# SYSTEM.net
KiCad netlist of a schematic drawn in Altium Designer
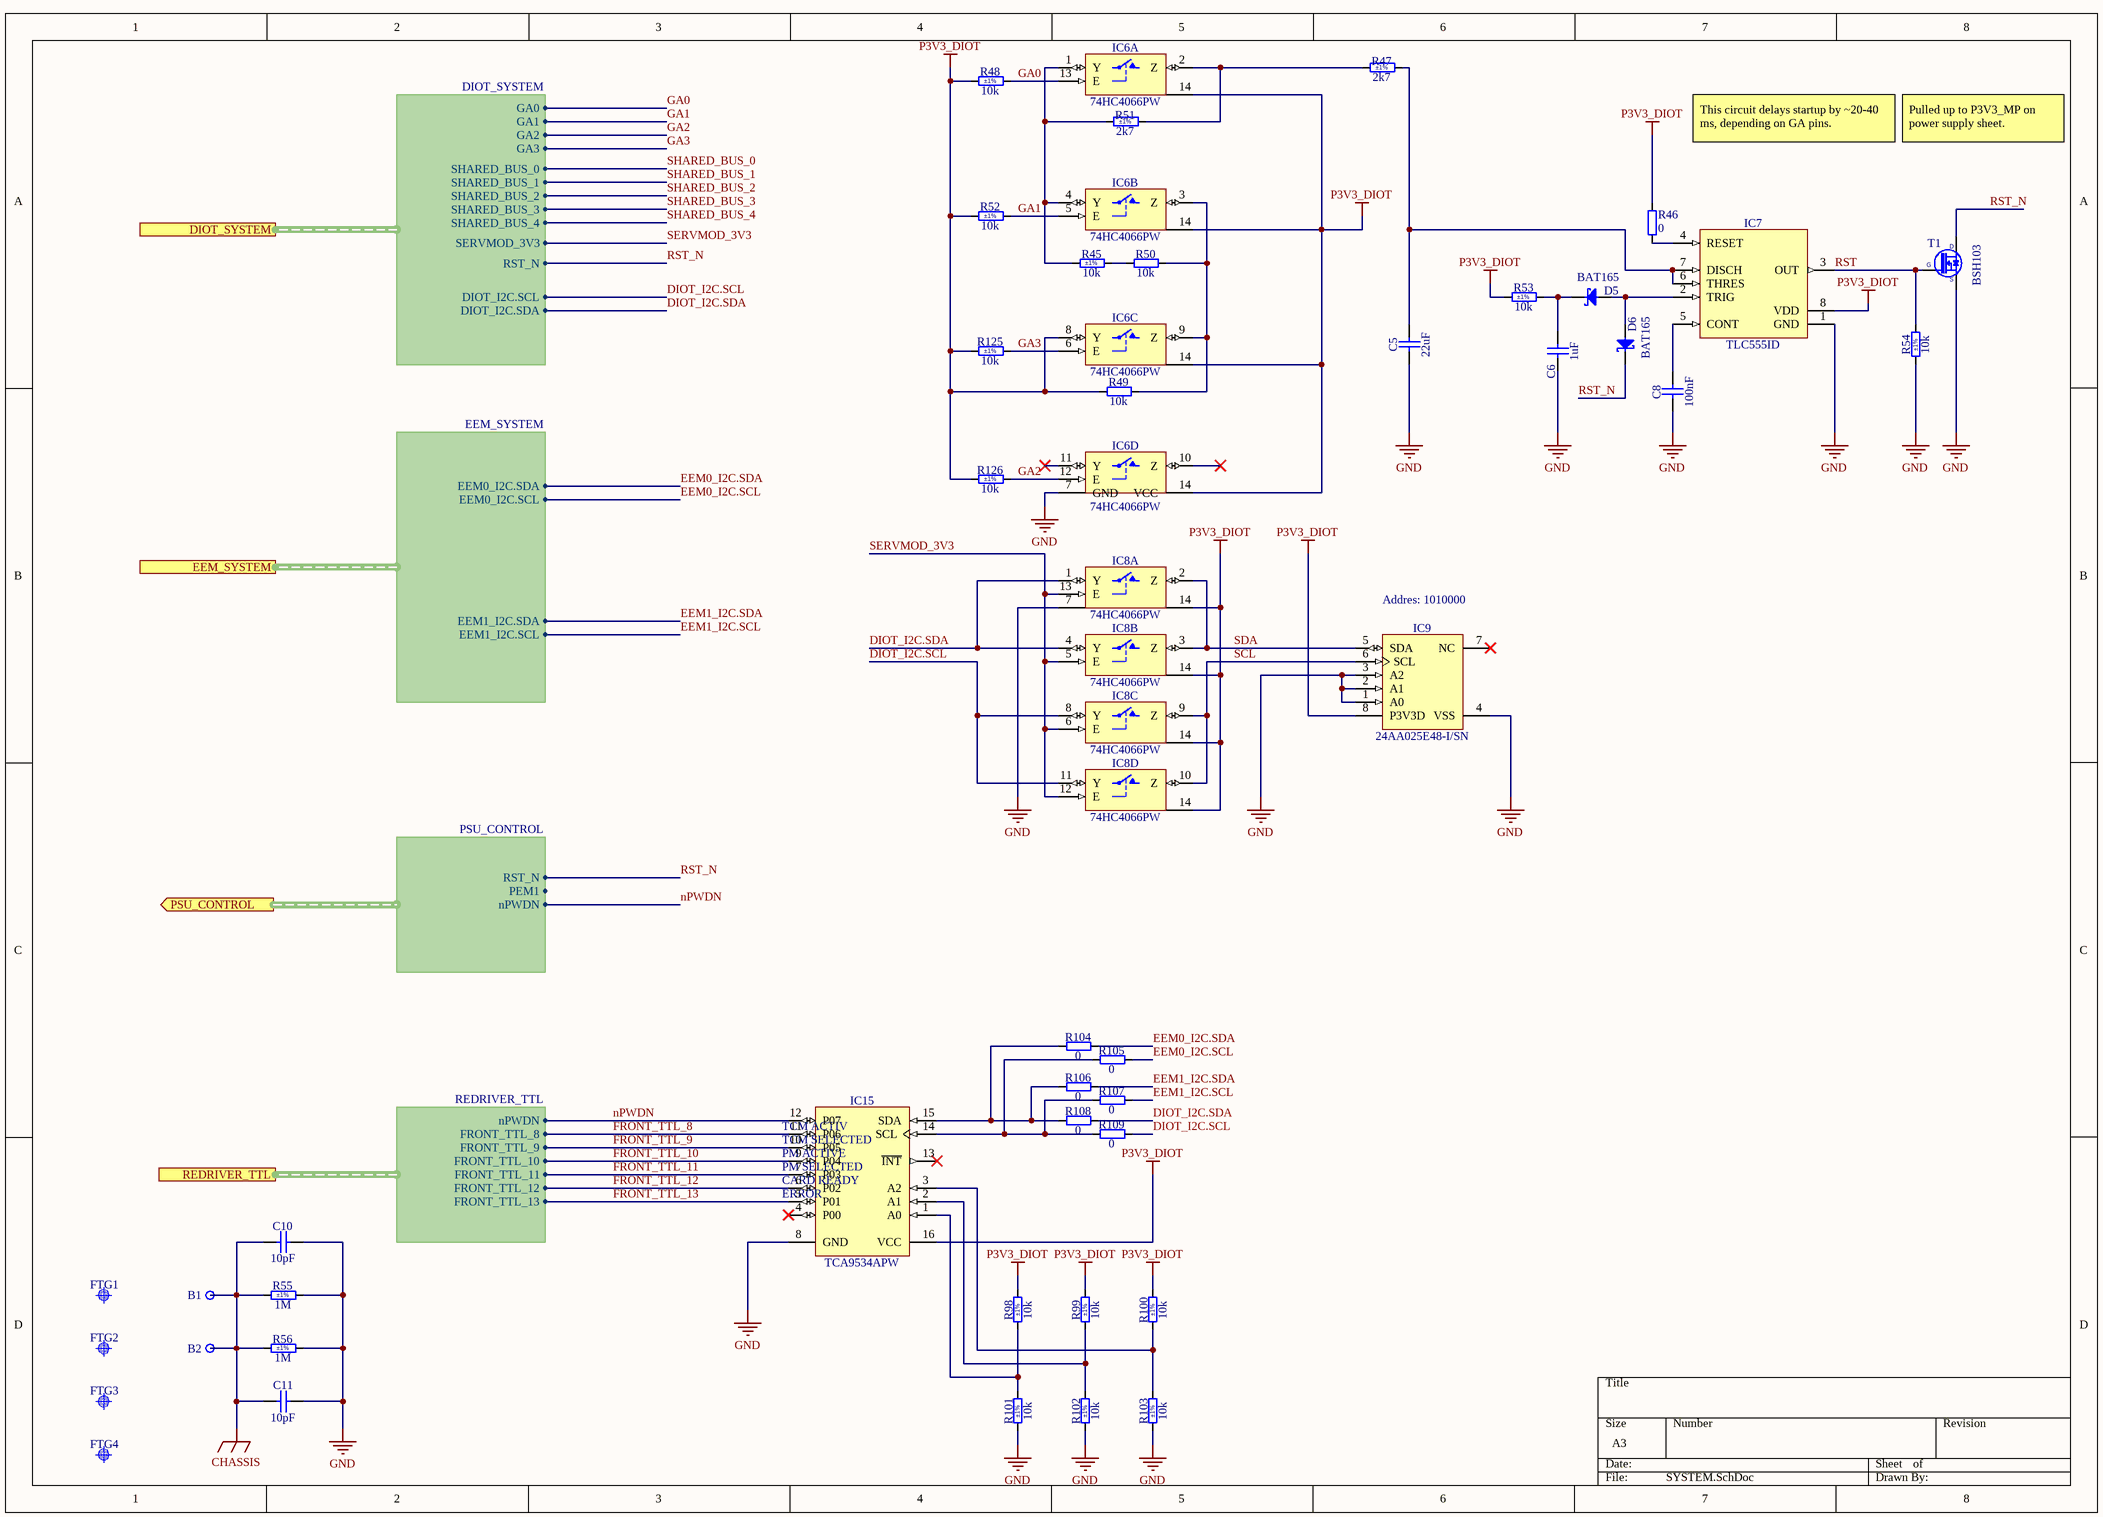
[diagram p0: SYSTEM.SchDoc]

(export (version "E")
  (design (tool "Eeschema 10.0.6"))
  (components
    (comp (ref "B1")
      (value "Plated Hole")
      (footprint "MTG320_550")
      (description "Single Terminal Socket")
      (fields (field (name "PART NUMBER") "PLATED_HOLE3.2_PAD5.5") (field (name "AUTHOR") "CERN DEM JMW"))
      (libsource (lib "Eletro-mechanical") (part "Single Terminal Socket"))
    )
    (comp (ref "B2")
      (value "Plated Hole")
      (footprint "MTG320_550")
      (description "Single Terminal Socket")
      (fields (field (name "PART NUMBER") "PLATED_HOLE3.2_PAD5.5") (field (name "AUTHOR") "CERN DEM JMW"))
      (libsource (lib "Eletro-mechanical") (part "Single Terminal Socket"))
    )
    (comp (ref "C5")
      (value "22uF")
      (footprint "CAPC1608X90N")
      (description "Non-polarised capacitor")
      (fields
        (field (name "MANUFACTURER") "GENERIC")
        (field (name "PART NUMBER") "CC0603_22UF_6.3V_20%_X5R")
        (field (name "AUTHOR") "CERN DEM JLC")
      )
      (libsource (lib "Capacitors") (part "Capacitor - non polarized"))
    )
    (comp (ref "C6")
      (value "1uF")
      (footprint "CAPC1005X55N")
      (description "Non-polarised capacitor")
      (fields
        (field (name "PART NUMBER") "CC0402_1UF_16V_10%_X5R")
        (field (name "VOLTAGE") "16V")
        (field (name "AUTHOR") "CERN DEM JLC")
      )
      (libsource (lib "Capacitors") (part "Capacitor - non polarized"))
    )
    (comp (ref "C8")
      (value "100nF")
      (footprint "CAPC1005X55N")
      (description "Non-polarised capacitor")
      (fields
        (field (name "PART NUMBER") "CC0402_100NF_16V_10%_X5R")
        (field (name "VOLTAGE") "16V")
        (field (name "AUTHOR") "CERN DEM JLC")
      )
      (libsource (lib "Capacitors") (part "Capacitor - non polarized"))
    )
    (comp (ref "C10")
      (value "10pF")
      (footprint "CAPC2013X100N")
      (description "Non-polarised capacitor")
      (fields
        (field (name "PART NUMBER") "CC0805_10PF_250V_5%_C0G_KEMET_HiQ-CBR")
        (field (name "VOLTAGE") "250V")
        (field (name "AUTHOR") "CERN DEM JLC")
      )
      (libsource (lib "Capacitors") (part "Capacitor - non polarized"))
    )
    (comp (ref "C11")
      (value "10pF")
      (footprint "CAPC2013X100N")
      (description "Non-polarised capacitor")
      (fields
        (field (name "PART NUMBER") "CC0805_10PF_250V_5%_C0G_KEMET_HiQ-CBR")
        (field (name "VOLTAGE") "250V")
        (field (name "AUTHOR") "CERN DEM JLC")
      )
      (libsource (lib "Capacitors") (part "Capacitor - non polarized"))
    )
    (comp (ref "D5")
      (value "BAT165")
      (footprint "SOD2512X110N")
      (description "Schottky Diode")
      (fields
        (field (name "VOLTAGE") "40V")
        (field (name "POWER") "750mA")
        (field (name "AUTHOR") "CERN DEM JLC")
      )
      (libsource (lib "ICs And Semiconductors") (part "Diode Schottky"))
    )
    (comp (ref "D6")
      (value "BAT165")
      (footprint "SOD2512X110N")
      (description "Schottky Diode")
      (fields
        (field (name "VOLTAGE") "40V")
        (field (name "POWER") "750mA")
        (field (name "AUTHOR") "CERN DEM JLC")
      )
      (libsource (lib "ICs And Semiconductors") (part "Diode Schottky"))
    )
    (comp (ref "FTG1")
      (value "Use only in PCB")
      (footprint "FIDUCIAL_TOP_C100-200")
      (description "Fiducial Target")
      (fields (field (name "PART NUMBER") "FIDUCIAL_TARGET_C100-200") (field (name "AUTHOR") "CERN DEM JLC"))
      (libsource (lib "Eletro-mechanical") (part "Fiducial Target"))
    )
    (comp (ref "FTG2")
      (value "Use only in PCB")
      (footprint "FIDUCIAL_TOP_C100-200")
      (description "Fiducial Target")
      (fields (field (name "PART NUMBER") "FIDUCIAL_TARGET_C100-200") (field (name "AUTHOR") "CERN DEM JLC"))
      (libsource (lib "Eletro-mechanical") (part "Fiducial Target"))
    )
    (comp (ref "FTG3")
      (value "Use only in PCB")
      (footprint "FIDUCIAL_TOP_C100-200")
      (description "Fiducial Target")
      (fields (field (name "PART NUMBER") "FIDUCIAL_TARGET_C100-200") (field (name "AUTHOR") "CERN DEM JLC"))
      (libsource (lib "Eletro-mechanical") (part "Fiducial Target"))
    )
    (comp (ref "FTG4")
      (value "Use only in PCB")
      (footprint "FIDUCIAL_TOP_C100-200")
      (description "Fiducial Target")
      (fields (field (name "PART NUMBER") "FIDUCIAL_TARGET_C100-200") (field (name "AUTHOR") "CERN DEM JLC"))
      (libsource (lib "Eletro-mechanical") (part "Fiducial Target"))
    )
    (comp (ref "IC6")
      (value "74HC4066PW")
      (footprint "SOP65P640X110-14N")
      (fields (field (name "MANUFACTURER") "NXP SEMICONDUCTORS") (field (name "AUTHOR") "CERN DEM JLC"))
      (libsource (lib "ICs And Semiconductors") (part "4066"))
    )
    (comp (ref "IC7")
      (value "TLC555ID")
      (footprint "SOIC127P600X175-8N")
      (description "LinCMOS Timer")
      (fields (field (name "MANUFACTURER") "TEXAS INSTRUMENTS") (field (name "AUTHOR") "CERN DEM JMW"))
      (libsource (lib "ICs And Semiconductors") (part "TLC555"))
    )
    (comp (ref "IC8")
      (value "74HC4066PW")
      (footprint "SOP65P640X110-14N")
      (fields (field (name "MANUFACTURER") "NXP SEMICONDUCTORS") (field (name "AUTHOR") "CERN DEM JLC"))
      (libsource (lib "ICs And Semiconductors") (part "4066"))
    )
    (comp (ref "IC9")
      (value "24AA025E48-I/SN")
      (footprint "SOIC127P600X175-8N")
      (description "1.7V-5.5V, 2K I2C™ Serial EEPROMs with EUI-48™ Node Identity")
      (fields (field (name "MANUFACTURER") "MICROCHIP TECHNOLOGY") (field (name "AUTHOR") "CERN DEM MR"))
      (libsource (lib "ICs And Semiconductors") (part "24AA025E48-I/SN"))
    )
    (comp (ref "IC15")
      (value "TCA9534APW")
      (footprint "SOP65P640X120-16N")
      (fields (field (name "MANUFACTURER") "TEXAS INSTRUMENTS") (field (name "AUTHOR") "CERN DEM BC"))
      (libsource (lib "ICs And Semiconductors") (part "TCA9534A"))
    )
    (comp (ref "R45")
      (value "10k")
      (footprint "RESC1005X40N")
      (description "Resistor - 1%")
      (fields
        (field (name "PART NUMBER") "R0402_10K_1%_0.0625W_100PPM")
        (field (name "POWER") "0.0625W")
        (field (name "TOLERANCE") "±1%")
        (field (name "AUTHOR") "CERN DEM JLC")
      )
      (libsource (lib "Resistors") (part "Resistor - 1%"))
    )
    (comp (ref "R46")
      (value "0")
      (footprint "RESC1005X40N")
      (description "Resistor")
      (fields
        (field (name "PART NUMBER") "R0402_0R_JUMPER")
        (field (name "MANUFACTURER") "GENERIC")
        (field (name "AUTHOR") "CERN DEM JLC")
      )
      (libsource (lib "Resistors") (part "Resistor"))
    )
    (comp (ref "R47")
      (value "2k7")
      (footprint "RESC1608X55N")
      (description "Resistor - 1%")
      (fields
        (field (name "PART NUMBER") "R0603_2K7_1%_0.1W_100PPM")
        (field (name "POWER") "0.1W")
        (field (name "TOLERANCE") "±1%")
        (field (name "AUTHOR") "CERN DEM JLC")
      )
      (libsource (lib "Resistors") (part "Resistor - 1%"))
    )
    (comp (ref "R48")
      (value "10k")
      (footprint "RESC1005X40N")
      (description "Resistor - 1%")
      (fields
        (field (name "PART NUMBER") "R0402_10K_1%_0.0625W_100PPM")
        (field (name "POWER") "0.0625W")
        (field (name "TOLERANCE") "±1%")
        (field (name "AUTHOR") "CERN DEM JLC")
      )
      (libsource (lib "Resistors") (part "Resistor - 1%"))
    )
    (comp (ref "R49")
      (value "10k")
      (footprint "RESC1005X40N")
      (description "Resistor - 1%")
      (fields
        (field (name "PART NUMBER") "R0402_10K_1%_0.0625W_100PPM")
        (field (name "POWER") "0.0625W")
        (field (name "AUTHOR") "CERN DEM JLC")
      )
      (libsource (lib "Resistors") (part "Resistor - 1%"))
    )
    (comp (ref "R50")
      (value "10k")
      (footprint "RESC1005X40N")
      (description "Resistor - 1%")
      (fields
        (field (name "PART NUMBER") "R0402_10K_1%_0.0625W_100PPM")
        (field (name "POWER") "0.0625W")
        (field (name "AUTHOR") "CERN DEM JLC")
      )
      (libsource (lib "Resistors") (part "Resistor - 1%"))
    )
    (comp (ref "R51")
      (value "2k7")
      (footprint "RESC1608X55N")
      (description "Resistor - 1%")
      (fields
        (field (name "PART NUMBER") "R0603_2K7_1%_0.1W_100PPM")
        (field (name "POWER") "0.1W")
        (field (name "TOLERANCE") "±1%")
        (field (name "AUTHOR") "CERN DEM JLC")
      )
      (libsource (lib "Resistors") (part "Resistor - 1%"))
    )
    (comp (ref "R52")
      (value "10k")
      (footprint "RESC1005X40N")
      (description "Resistor - 1%")
      (fields
        (field (name "PART NUMBER") "R0402_10K_1%_0.0625W_100PPM")
        (field (name "POWER") "0.0625W")
        (field (name "TOLERANCE") "±1%")
        (field (name "AUTHOR") "CERN DEM JLC")
      )
      (libsource (lib "Resistors") (part "Resistor - 1%"))
    )
    (comp (ref "R53")
      (value "10k")
      (footprint "RESC1005X40N")
      (description "Resistor - 1%")
      (fields
        (field (name "TOLERANCE") "±1%")
        (field (name "PART NUMBER") "R0402_10K_1%_0.0625W_100PPM")
        (field (name "POWER") "0.0625W")
        (field (name "AUTHOR") "CERN DEM JLC")
      )
      (libsource (lib "Resistors") (part "Resistor - 1%"))
    )
    (comp (ref "R54")
      (value "10k")
      (footprint "RESC1005X40N")
      (description "Resistor - 1%")
      (fields
        (field (name "TOLERANCE") "±1%")
        (field (name "PART NUMBER") "R0402_10K_1%_0.0625W_100PPM")
        (field (name "POWER") "0.0625W")
        (field (name "AUTHOR") "CERN DEM JLC")
      )
      (libsource (lib "Resistors") (part "Resistor - 1%"))
    )
    (comp (ref "R55")
      (value "1M")
      (footprint "RESC2012X60N")
      (description "Resistor - 1%")
      (fields
        (field (name "TOLERANCE") "±1%")
        (field (name "PART NUMBER") "R0805_1M_1%_0.125W_100PPM")
        (field (name "POWER") "0.125W")
        (field (name "AUTHOR") "CERN DEM JLC")
      )
      (libsource (lib "Resistors") (part "Resistor - 1%"))
    )
    (comp (ref "R56")
      (value "1M")
      (footprint "RESC2012X60N")
      (description "Resistor - 1%")
      (fields
        (field (name "TOLERANCE") "±1%")
        (field (name "PART NUMBER") "R0805_1M_1%_0.125W_100PPM")
        (field (name "POWER") "0.125W")
        (field (name "AUTHOR") "CERN DEM JLC")
      )
      (libsource (lib "Resistors") (part "Resistor - 1%"))
    )
    (comp (ref "R98")
      (value "10k")
      (footprint "RESC1608X55N")
      (description "Resistor - 1%")
      (fields
        (field (name "TOLERANCE") "±1%")
        (field (name "PART NUMBER") "R0603_10K_1%_0.1W_100PPM")
        (field (name "POWER") "0.1W")
        (field (name "AUTHOR") "CERN DEM JLC")
      )
      (libsource (lib "Resistors") (part "Resistor - 1%"))
    )
    (comp (ref "R99")
      (value "10k")
      (footprint "RESC1608X55N")
      (description "Resistor - 1%")
      (fields
        (field (name "TOLERANCE") "±1%")
        (field (name "PART NUMBER") "R0603_10K_1%_0.1W_100PPM")
        (field (name "POWER") "0.1W")
        (field (name "AUTHOR") "CERN DEM JLC")
      )
      (libsource (lib "Resistors") (part "Resistor - 1%"))
    )
    (comp (ref "R100")
      (value "10k")
      (footprint "RESC1608X55N")
      (description "Resistor - 1%")
      (fields
        (field (name "TOLERANCE") "±1%")
        (field (name "PART NUMBER") "R0603_10K_1%_0.1W_100PPM")
        (field (name "POWER") "0.1W")
        (field (name "AUTHOR") "CERN DEM JLC")
      )
      (libsource (lib "Resistors") (part "Resistor - 1%"))
    )
    (comp (ref "R101")
      (value "10k")
      (footprint "RESC1608X55N")
      (description "Resistor - 1%")
      (fields
        (field (name "TOLERANCE") "±1%")
        (field (name "PART NUMBER") "R0603_10K_1%_0.1W_100PPM")
        (field (name "POWER") "0.1W")
        (field (name "AUTHOR") "CERN DEM JLC")
      )
      (libsource (lib "Resistors") (part "Resistor - 1%"))
    )
    (comp (ref "R102")
      (value "10k")
      (footprint "RESC1608X55N")
      (description "Resistor - 1%")
      (fields
        (field (name "TOLERANCE") "±1%")
        (field (name "PART NUMBER") "R0603_10K_1%_0.1W_100PPM")
        (field (name "POWER") "0.1W")
        (field (name "AUTHOR") "CERN DEM JLC")
      )
      (libsource (lib "Resistors") (part "Resistor - 1%"))
    )
    (comp (ref "R103")
      (value "10k")
      (footprint "RESC1608X55N")
      (description "Resistor - 1%")
      (fields
        (field (name "TOLERANCE") "±1%")
        (field (name "PART NUMBER") "R0603_10K_1%_0.1W_100PPM")
        (field (name "POWER") "0.1W")
        (field (name "AUTHOR") "CERN DEM JLC")
      )
      (libsource (lib "Resistors") (part "Resistor - 1%"))
    )
    (comp (ref "R104")
      (value "0")
      (footprint "RESC1608X55N")
      (description "Resistor")
      (fields
        (field (name "PART NUMBER") "R0603_0R_JUMPER")
        (field (name "MANUFACTURER") "GENERIC")
        (field (name "AUTHOR") "CERN DEM JLC")
      )
      (libsource (lib "Resistors") (part "Resistor"))
    )
    (comp (ref "R105")
      (value "0")
      (footprint "RESC1608X55N")
      (description "Resistor")
      (fields
        (field (name "PART NUMBER") "R0603_0R_JUMPER")
        (field (name "MANUFACTURER") "GENERIC")
        (field (name "AUTHOR") "CERN DEM JLC")
      )
      (libsource (lib "Resistors") (part "Resistor"))
    )
    (comp (ref "R106")
      (value "0")
      (footprint "RESC1608X55N")
      (description "Resistor")
      (fields
        (field (name "PART NUMBER") "R0603_0R_JUMPER")
        (field (name "MANUFACTURER") "GENERIC")
        (field (name "AUTHOR") "CERN DEM JLC")
      )
      (libsource (lib "Resistors") (part "Resistor"))
    )
    (comp (ref "R107")
      (value "0")
      (footprint "RESC1608X55N")
      (description "Resistor")
      (fields
        (field (name "PART NUMBER") "R0603_0R_JUMPER")
        (field (name "MANUFACTURER") "GENERIC")
        (field (name "AUTHOR") "CERN DEM JLC")
      )
      (libsource (lib "Resistors") (part "Resistor"))
    )
    (comp (ref "R108")
      (value "0")
      (footprint "RESC1608X55N")
      (description "Resistor")
      (fields
        (field (name "PART NUMBER") "R0603_0R_JUMPER")
        (field (name "MANUFACTURER") "GENERIC")
        (field (name "AUTHOR") "CERN DEM JLC")
      )
      (libsource (lib "Resistors") (part "Resistor"))
    )
    (comp (ref "R109")
      (value "0")
      (footprint "RESC1608X55N")
      (description "Resistor")
      (fields
        (field (name "PART NUMBER") "R0603_0R_JUMPER")
        (field (name "MANUFACTURER") "GENERIC")
        (field (name "AUTHOR") "CERN DEM JLC")
      )
      (libsource (lib "Resistors") (part "Resistor"))
    )
    (comp (ref "R125")
      (value "10k")
      (footprint "RESC1005X40N")
      (description "Resistor - 1%")
      (fields
        (field (name "PART NUMBER") "R0402_10K_1%_0.0625W_100PPM")
        (field (name "POWER") "0.0625W")
        (field (name "TOLERANCE") "±1%")
        (field (name "AUTHOR") "CERN DEM JLC")
      )
      (libsource (lib "Resistors") (part "Resistor - 1%"))
    )
    (comp (ref "R126")
      (value "10k")
      (footprint "RESC1005X40N")
      (description "Resistor - 1%")
      (fields
        (field (name "PART NUMBER") "R0402_10K_1%_0.0625W_100PPM")
        (field (name "POWER") "0.0625W")
        (field (name "TOLERANCE") "±1%")
        (field (name "AUTHOR") "CERN DEM JLC")
      )
      (libsource (lib "Resistors") (part "Resistor - 1%"))
    )
    (comp (ref "T1")
      (value "BSH103")
      (footprint "SOT95P230X110-3N")
      (description "N-CHANNEL MOSFET WITH DIODE")
      (fields (field (name "MANUFACTURER") "NEXPERIA") (field (name "AUTHOR") "CERN DEM JLC"))
      (libsource (lib "ICs And Semiconductors") (part "N-MOSFET-D 1G 2S 3D"))
    )
  )
  (nets
    (net (code "5") (name "/DIOT_I2C.SCL") (class "Default")
      (node (ref "IC8") (pin "11") (pinfunction "Y_11") (pintype "bidirectional"))
      (node (ref "IC8") (pin "8") (pinfunction "Y_8") (pintype "bidirectional"))
      (node (ref "R109") (pin "2") (pinfunction "2_2") (pintype "passive"))
    )
    (net (code "6") (name "/DIOT_I2C.SDA") (class "Default")
      (node (ref "IC8") (pin "1") (pinfunction "Y_1") (pintype "bidirectional"))
      (node (ref "IC8") (pin "4") (pinfunction "Y_4") (pintype "bidirectional"))
      (node (ref "R108") (pin "2") (pinfunction "2_2") (pintype "passive"))
    )
    (net (code "7") (name "/EEM0_I2C.SCL") (class "Default")
      (node (ref "R105") (pin "2") (pinfunction "2_2") (pintype "passive"))
    )
    (net (code "8") (name "/EEM0_I2C.SDA") (class "Default")
      (node (ref "R104") (pin "2") (pinfunction "2_2") (pintype "passive"))
    )
    (net (code "9") (name "/EEM1_I2C.SCL") (class "Default")
      (node (ref "R107") (pin "2") (pinfunction "2_2") (pintype "passive"))
    )
    (net (code "10") (name "/EEM1_I2C.SDA") (class "Default")
      (node (ref "R106") (pin "2") (pinfunction "2_2") (pintype "passive"))
    )
    (net (code "11") (name "/FRONT_TTL_8") (class "Default")
      (node (ref "IC15") (pin "11") (pinfunction "P06_11") (pintype "bidirectional"))
    )
    (net (code "12") (name "/FRONT_TTL_9") (class "Default")
      (node (ref "IC15") (pin "10") (pinfunction "P05_10") (pintype "bidirectional"))
    )
    (net (code "13") (name "/FRONT_TTL_10") (class "Default")
      (node (ref "IC15") (pin "9") (pinfunction "P04_9") (pintype "bidirectional"))
    )
    (net (code "14") (name "/FRONT_TTL_11") (class "Default")
      (node (ref "IC15") (pin "7") (pinfunction "P03_7") (pintype "bidirectional"))
    )
    (net (code "15") (name "/FRONT_TTL_12") (class "Default")
      (node (ref "IC15") (pin "6") (pinfunction "P02_6") (pintype "bidirectional"))
    )
    (net (code "16") (name "/FRONT_TTL_13") (class "Default")
      (node (ref "IC15") (pin "5") (pinfunction "P01_5") (pintype "bidirectional"))
    )
    (net (code "17") (name "/GA0") (class "Default")
      (node (ref "IC6") (pin "13") (pinfunction "E_13") (pintype "input"))
      (node (ref "R48") (pin "2") (pinfunction "2_2") (pintype "passive"))
    )
    (net (code "18") (name "/GA1") (class "Default")
      (node (ref "IC6") (pin "5") (pinfunction "E_5") (pintype "input"))
      (node (ref "R52") (pin "2") (pinfunction "2_2") (pintype "passive"))
    )
    (net (code "19") (name "/GA2") (class "Default")
      (node (ref "IC6") (pin "12") (pinfunction "E_12") (pintype "input"))
      (node (ref "R126") (pin "2") (pinfunction "2_2") (pintype "passive"))
    )
    (net (code "20") (name "/GA3") (class "Default")
      (node (ref "IC6") (pin "6") (pinfunction "E_6") (pintype "input"))
      (node (ref "R125") (pin "2") (pinfunction "2_2") (pintype "passive"))
    )
    (net (code "21") (name "/RST") (class "Default")
      (node (ref "IC7") (pin "3") (pinfunction "OUT_3") (pintype "output"))
      (node (ref "R54") (pin "2") (pinfunction "2_2") (pintype "passive"))
      (node (ref "T1") (pin "1") (pinfunction "G_1") (pintype "passive"))
    )
    (net (code "22") (name "/RST_N") (class "Default")
      (node (ref "D6") (pin "1") (pinfunction "C_1") (pintype "passive"))
      (node (ref "T1") (pin "3") (pinfunction "D_3") (pintype "passive"))
    )
    (net (code "23") (name "/SCL") (class "Default")
      (node (ref "IC8") (pin "10") (pinfunction "Z_10") (pintype "bidirectional"))
      (node (ref "IC8") (pin "9") (pinfunction "Z_9") (pintype "bidirectional"))
      (node (ref "IC9") (pin "6") (pinfunction "SCL_6") (pintype "input"))
    )
    (net (code "24") (name "/SDA") (class "Default")
      (node (ref "IC8") (pin "2") (pinfunction "Z_2") (pintype "bidirectional"))
      (node (ref "IC8") (pin "3") (pinfunction "Z_3") (pintype "bidirectional"))
      (node (ref "IC9") (pin "5") (pinfunction "SDA_5") (pintype "bidirectional"))
    )
    (net (code "25") (name "/SERVMOD_3V3") (class "Default")
      (node (ref "IC8") (pin "12") (pinfunction "E_12") (pintype "input"))
      (node (ref "IC8") (pin "13") (pinfunction "E_13") (pintype "input"))
      (node (ref "IC8") (pin "5") (pinfunction "E_5") (pintype "input"))
      (node (ref "IC8") (pin "6") (pinfunction "E_6") (pintype "input"))
    )
    (net (code "31") (name "/nPWDN") (class "Default")
      (node (ref "IC15") (pin "12") (pinfunction "P07_12") (pintype "bidirectional"))
    )
    (net (code "36") (name "CHASSIS") (class "Default")
      (node (ref "B1") (pin "1") (pinfunction "1_1") (pintype "bidirectional"))
      (node (ref "B2") (pin "1") (pinfunction "1_1") (pintype "bidirectional"))
      (node (ref "C10") (pin "1") (pinfunction "1_1") (pintype "passive"))
      (node (ref "C11") (pin "1") (pinfunction "1_1") (pintype "passive"))
      (node (ref "R55") (pin "1") (pinfunction "1_1") (pintype "passive"))
      (node (ref "R56") (pin "1") (pinfunction "1_1") (pintype "passive"))
    )
    (net (code "37") (name "GND") (class "Default")
      (node (ref "C10") (pin "2") (pinfunction "2_2") (pintype "passive"))
      (node (ref "C11") (pin "2") (pinfunction "2_2") (pintype "passive"))
      (node (ref "C5") (pin "1") (pinfunction "1_1") (pintype "passive"))
      (node (ref "C6") (pin "1") (pinfunction "1_1") (pintype "passive"))
      (node (ref "C8") (pin "1") (pinfunction "1_1") (pintype "passive"))
      (node (ref "IC15") (pin "8") (pinfunction "GND_8") (pintype "power_in"))
      (node (ref "IC6") (pin "7") (pinfunction "GND_7") (pintype "power_in"))
      (node (ref "IC7") (pin "1") (pinfunction "GND_1") (pintype "power_in"))
      (node (ref "IC8") (pin "7") (pinfunction "GND_7") (pintype "power_in"))
      (node (ref "IC9") (pin "1") (pinfunction "A0_1") (pintype "input"))
      (node (ref "IC9") (pin "2") (pinfunction "A1_2") (pintype "input"))
      (node (ref "IC9") (pin "3") (pinfunction "A2_3") (pintype "input"))
      (node (ref "IC9") (pin "4") (pinfunction "VSS_4") (pintype "power_in"))
      (node (ref "R101") (pin "1") (pinfunction "1_1") (pintype "passive"))
      (node (ref "R102") (pin "1") (pinfunction "1_1") (pintype "passive"))
      (node (ref "R103") (pin "1") (pinfunction "1_1") (pintype "passive"))
      (node (ref "R54") (pin "1") (pinfunction "1_1") (pintype "passive"))
      (node (ref "R55") (pin "2") (pinfunction "2_2") (pintype "passive"))
      (node (ref "R56") (pin "2") (pinfunction "2_2") (pintype "passive"))
      (node (ref "T1") (pin "2") (pinfunction "S_2") (pintype "passive"))
    )
    (net (code "38") (name "Net-(D5-A)") (class "Default")
      (node (ref "D5") (pin "2") (pinfunction "A_2") (pintype "passive"))
      (node (ref "D6") (pin "2") (pinfunction "A_2") (pintype "passive"))
      (node (ref "IC7") (pin "2") (pinfunction "TRIG_2") (pintype "input"))
    )
    (net (code "39") (name "Net-(D5-C)") (class "Default")
      (node (ref "C6") (pin "2") (pinfunction "2_2") (pintype "passive"))
      (node (ref "D5") (pin "1") (pinfunction "C_1") (pintype "passive"))
      (node (ref "R53") (pin "2") (pinfunction "2_2") (pintype "passive"))
    )
    (net (code "40") (name "Net-(IC6A-Y)") (class "Default")
      (node (ref "IC6") (pin "1") (pinfunction "Y_1") (pintype "bidirectional"))
      (node (ref "IC6") (pin "4") (pinfunction "Y_4") (pintype "bidirectional"))
      (node (ref "R45") (pin "2") (pinfunction "2_2") (pintype "passive"))
      (node (ref "R51") (pin "1") (pinfunction "1_1") (pintype "passive"))
    )
    (net (code "41") (name "Net-(IC6A-Z)") (class "Default")
      (node (ref "IC6") (pin "2") (pinfunction "Z_2") (pintype "bidirectional"))
      (node (ref "R47") (pin "1") (pinfunction "1_1") (pintype "passive"))
      (node (ref "R51") (pin "2") (pinfunction "2_2") (pintype "passive"))
    )
    (net (code "42") (name "Net-(IC6B-Z)") (class "Default")
      (node (ref "IC6") (pin "3") (pinfunction "Z_3") (pintype "bidirectional"))
      (node (ref "IC6") (pin "9") (pinfunction "Z_9") (pintype "bidirectional"))
      (node (ref "R49") (pin "2") (pinfunction "2_2") (pintype "passive"))
      (node (ref "R50") (pin "2") (pinfunction "2_2") (pintype "passive"))
    )
    (net (code "43") (name "Net-(IC7-CONT)") (class "Default")
      (node (ref "C8") (pin "2") (pinfunction "2_2") (pintype "passive"))
      (node (ref "IC7") (pin "5") (pinfunction "CONT_5") (pintype "input"))
    )
    (net (code "44") (name "Net-(IC7-DISCH)") (class "Default")
      (node (ref "C5") (pin "2") (pinfunction "2_2") (pintype "passive"))
      (node (ref "IC7") (pin "6") (pinfunction "THRES_6") (pintype "input"))
      (node (ref "IC7") (pin "7") (pinfunction "DISCH_7") (pintype "input"))
      (node (ref "R47") (pin "2") (pinfunction "2_2") (pintype "passive"))
    )
    (net (code "45") (name "Net-(IC7-RESET)") (class "Default")
      (node (ref "IC7") (pin "4") (pinfunction "RESET_4") (pintype "input"))
      (node (ref "R46") (pin "1") (pinfunction "1_1") (pintype "passive"))
    )
    (net (code "46") (name "Net-(IC15-A0)") (class "Default")
      (node (ref "IC15") (pin "1") (pinfunction "A0_1") (pintype "input"))
      (node (ref "R101") (pin "2") (pinfunction "2_2") (pintype "passive"))
      (node (ref "R98") (pin "1") (pinfunction "1_1") (pintype "passive"))
    )
    (net (code "47") (name "Net-(IC15-A1)") (class "Default")
      (node (ref "IC15") (pin "2") (pinfunction "A1_2") (pintype "input"))
      (node (ref "R102") (pin "2") (pinfunction "2_2") (pintype "passive"))
      (node (ref "R99") (pin "1") (pinfunction "1_1") (pintype "passive"))
    )
    (net (code "48") (name "Net-(IC15-A2)") (class "Default")
      (node (ref "IC15") (pin "3") (pinfunction "A2_3") (pintype "input"))
      (node (ref "R100") (pin "1") (pinfunction "1_1") (pintype "passive"))
      (node (ref "R103") (pin "2") (pinfunction "2_2") (pintype "passive"))
    )
    (net (code "49") (name "Net-(IC15-SCL)") (class "Default")
      (node (ref "IC15") (pin "14") (pinfunction "SCL_14") (pintype "input"))
      (node (ref "R105") (pin "1") (pinfunction "1_1") (pintype "passive"))
      (node (ref "R107") (pin "1") (pinfunction "1_1") (pintype "passive"))
      (node (ref "R109") (pin "1") (pinfunction "1_1") (pintype "passive"))
    )
    (net (code "50") (name "Net-(IC15-SDA)") (class "Default")
      (node (ref "IC15") (pin "15") (pinfunction "SDA_15") (pintype "input"))
      (node (ref "R104") (pin "1") (pinfunction "1_1") (pintype "passive"))
      (node (ref "R106") (pin "1") (pinfunction "1_1") (pintype "passive"))
      (node (ref "R108") (pin "1") (pinfunction "1_1") (pintype "passive"))
    )
    (net (code "51") (name "Net-(R45-Pad1)") (class "Default")
      (node (ref "R45") (pin "1") (pinfunction "1_1") (pintype "passive"))
      (node (ref "R50") (pin "1") (pinfunction "1_1") (pintype "passive"))
    )
    (net (code "52") (name "P3V3_DIOT") (class "Default")
      (node (ref "IC15") (pin "16") (pinfunction "VCC_16") (pintype "power_in"))
      (node (ref "IC6") (pin "14") (pinfunction "VCC_14") (pintype "power_in"))
      (node (ref "IC6") (pin "8") (pinfunction "Y_8") (pintype "bidirectional"))
      (node (ref "IC7") (pin "8") (pinfunction "VDD_8") (pintype "power_in"))
      (node (ref "IC8") (pin "14") (pinfunction "VCC_14") (pintype "power_in"))
      (node (ref "IC9") (pin "8") (pinfunction "P3V3D_8") (pintype "power_in"))
      (node (ref "R100") (pin "2") (pinfunction "2_2") (pintype "passive"))
      (node (ref "R125") (pin "1") (pinfunction "1_1") (pintype "passive"))
      (node (ref "R126") (pin "1") (pinfunction "1_1") (pintype "passive"))
      (node (ref "R46") (pin "2") (pinfunction "2_2") (pintype "passive"))
      (node (ref "R48") (pin "1") (pinfunction "1_1") (pintype "passive"))
      (node (ref "R49") (pin "1") (pinfunction "1_1") (pintype "passive"))
      (node (ref "R52") (pin "1") (pinfunction "1_1") (pintype "passive"))
      (node (ref "R53") (pin "1") (pinfunction "1_1") (pintype "passive"))
      (node (ref "R98") (pin "2") (pinfunction "2_2") (pintype "passive"))
      (node (ref "R99") (pin "2") (pinfunction "2_2") (pintype "passive"))
    )
    (net (code "53") (name "unconnected-(IC6D-Y-Pad11)") (class "Default")
      (node (ref "IC6") (pin "11") (pinfunction "Y_11") (pintype "bidirectional+no_connect"))
    )
    (net (code "54") (name "unconnected-(IC6D-Z-Pad10)") (class "Default")
      (node (ref "IC6") (pin "10") (pinfunction "Z_10") (pintype "bidirectional+no_connect"))
    )
    (net (code "55") (name "unconnected-(IC9-NC-Pad7)") (class "Default")
      (node (ref "IC9") (pin "7") (pinfunction "NC_7") (pintype "passive+no_connect"))
    )
    (net (code "56") (name "unconnected-(IC15-P00-Pad4)") (class "Default")
      (node (ref "IC15") (pin "4") (pinfunction "P00_4") (pintype "bidirectional+no_connect"))
    )
    (net (code "57") (name "unconnected-(IC15-~{INT}-Pad13)") (class "Default")
      (node (ref "IC15") (pin "13") (pinfunction "~{INT}_13") (pintype "output+no_connect"))
    )
  )
)
